# Lithiumversion_2019_09_02.net
KiCad netlist of a schematic drawn in EAGLE
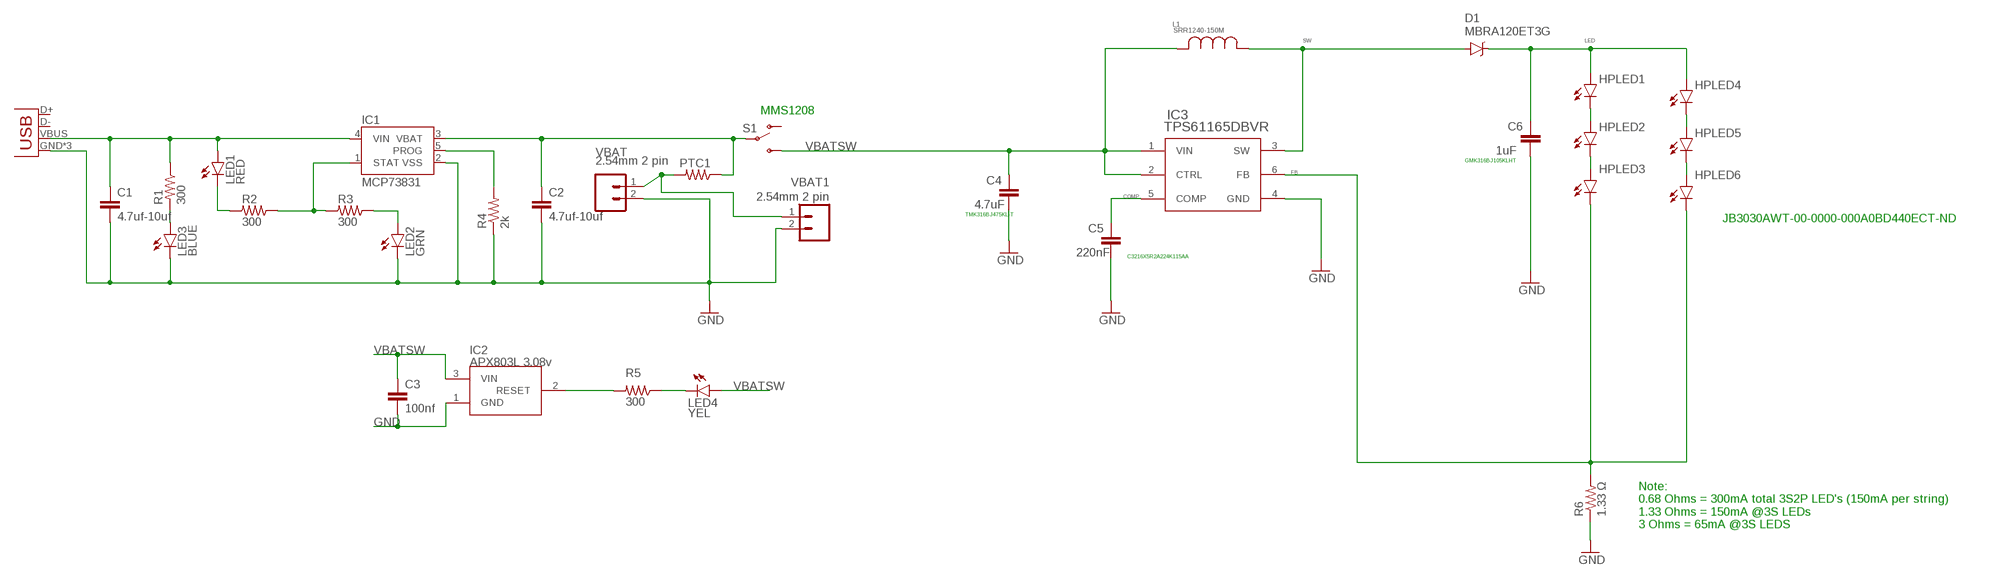
[diagram p0: schematic, sheet 1]

(export (version "E")
  (design (tool "Eeschema 10.0.6"))
  (components
    (comp (ref "C1")
      (value "4.7uf-10uf")
      (footprint "eagle-import:1206")
      (libsource (lib "eagle-import") (part "CAP1206"))
    )
    (comp (ref "C2")
      (value "4.7uf-10uf")
      (footprint "eagle-import:1206")
      (libsource (lib "eagle-import") (part "CAP1206"))
    )
    (comp (ref "C3")
      (value "100nf")
      (footprint "eagle-import:1206")
      (libsource (lib "eagle-import") (part "CAP1206"))
    )
    (comp (ref "C4")
      (value "4.7uF")
      (footprint "eagle-import:1206")
      (libsource (lib "eagle-import") (part "SparkFun-Passives_CAP1206"))
    )
    (comp (ref "C5")
      (value "220nF")
      (footprint "eagle-import:1206")
      (libsource (lib "eagle-import") (part "SparkFun-Passives_CAP1206"))
    )
    (comp (ref "C6")
      (value "1uF")
      (footprint "eagle-import:1206")
      (libsource (lib "eagle-import") (part "SparkFun-Passives_CAP1206"))
    )
    (comp (ref "D1")
      (value "MBRA120ET3G")
      (footprint "eagle-import:SMA-DIODE")
      (libsource (lib "eagle-import") (part "DIODE-SCHOTTKY-B340A"))
    )
    (comp (ref "HPLED1")
      (value "CREE_J_3030")
      (footprint "eagle-import:CREE_J_3030")
      (libsource (lib "eagle-import") (part "CREE_J_3030"))
    )
    (comp (ref "HPLED2")
      (value "CREE_J_3030")
      (footprint "eagle-import:CREE_J_3030")
      (libsource (lib "eagle-import") (part "CREE_J_3030"))
    )
    (comp (ref "HPLED3")
      (value "CREE_J_3030")
      (footprint "eagle-import:CREE_J_3030")
      (libsource (lib "eagle-import") (part "CREE_J_3030"))
    )
    (comp (ref "HPLED4")
      (value "CREE_J_3030")
      (footprint "eagle-import:CREE_J_3030")
      (libsource (lib "eagle-import") (part "CREE_J_3030"))
    )
    (comp (ref "HPLED5")
      (value "CREE_J_3030")
      (footprint "eagle-import:CREE_J_3030")
      (libsource (lib "eagle-import") (part "CREE_J_3030"))
    )
    (comp (ref "HPLED6")
      (value "CREE_J_3030")
      (footprint "eagle-import:CREE_J_3030")
      (libsource (lib "eagle-import") (part "CREE_J_3030"))
    )
    (comp (ref "IC1")
      (value "MCP73831")
      (footprint "eagle-import:SOT23-5")
      (libsource (lib "eagle-import") (part "MCP73831"))
    )
    (comp (ref "IC2")
      (value "APX803L 3.08v")
      (footprint "eagle-import:SOT23")
      (libsource (lib "eagle-import") (part "ADP160"))
    )
    (comp (ref "IC3")
      (value "TPS61165DBVR")
      (footprint "eagle-import:DBV6")
      (libsource (lib "eagle-import") (part "TPS61165DBVR"))
    )
    (comp (ref "JP3")
      (value "USB-MICROB")
      (footprint "eagle-import:USB-MICROB")
      (libsource (lib "eagle-import") (part "USB-MICROB"))
    )
    (comp (ref "L1")
      (value "SRR1240-150M")
      (footprint "eagle-import:IND_BOURNS_SRR1240")
      (fields (field (name "MANUFACTURER_PART_NUMBER") "SRR1240100M"))
      (libsource (lib "eagle-import") (part "SRR1240-100M"))
    )
    (comp (ref "LED1")
      (value "RED")
      (footprint "eagle-import:LED-1206")
      (libsource (lib "eagle-import") (part "LED1206"))
    )
    (comp (ref "LED2")
      (value "GRN")
      (footprint "eagle-import:LED-1206")
      (libsource (lib "eagle-import") (part "LED1206"))
    )
    (comp (ref "LED3")
      (value "BLUE")
      (footprint "eagle-import:LED-1206")
      (libsource (lib "eagle-import") (part "LED1206"))
    )
    (comp (ref "LED4")
      (value "YEL")
      (footprint "eagle-import:LED-1206")
      (libsource (lib "eagle-import") (part "LED1206"))
    )
    (comp (ref "PTC1")
      (value "RESISTOR1206")
      (footprint "eagle-import:1206")
      (libsource (lib "eagle-import") (part "SparkFun-Resistors_RESISTOR1206"))
    )
    (comp (ref "R1")
      (value "300")
      (footprint "eagle-import:1206")
      (libsource (lib "eagle-import") (part "SparkFun-Resistors_RESISTOR1206"))
    )
    (comp (ref "R2")
      (value "300")
      (footprint "eagle-import:1206")
      (libsource (lib "eagle-import") (part "SparkFun-Resistors_RESISTOR1206"))
    )
    (comp (ref "R3")
      (value "300")
      (footprint "eagle-import:1206")
      (libsource (lib "eagle-import") (part "SparkFun-Resistors_RESISTOR1206"))
    )
    (comp (ref "R4")
      (value "2k")
      (footprint "eagle-import:1206")
      (libsource (lib "eagle-import") (part "SparkFun-Resistors_RESISTOR1206"))
    )
    (comp (ref "R5")
      (value "300")
      (footprint "eagle-import:1206")
      (libsource (lib "eagle-import") (part "SparkFun-Resistors_RESISTOR1206"))
    )
    (comp (ref "R6")
      (value "1.33 Ω")
      (footprint "eagle-import:1206")
      (libsource (lib "eagle-import") (part "RESISTOR1206"))
    )
    (comp (ref "S1")
      (value "SWITCH-SPDTKIT")
      (footprint "eagle-import:SWITCH-SPDT_KIT")
      (libsource (lib "eagle-import") (part "SWITCH-SPDTKIT"))
    )
    (comp (ref "VBAT")
      (value "2.54mm 2 pin")
      (footprint "eagle-import:JST-2-PTH-VERT")
      (libsource (lib "eagle-import") (part "M02JST-PTH-VERT"))
    )
    (comp (ref "VBAT1")
      (value "2.54mm 2 pin")
      (footprint "eagle-import:JST-2-PTH-VERT")
      (libsource (lib "eagle-import") (part "M02JST-PTH-VERT"))
    )
  )
  (nets
    (net (code "1") (name "/COMP") (class "Default")
      (node (ref "C5") (pin "2") (pinfunction "2_2") (pintype "passive"))
      (node (ref "IC3") (pin "5") (pinfunction "COMP_5") (pintype "output"))
    )
    (net (code "2") (name "/FB") (class "Default")
      (node (ref "HPLED3") (pin "C") (pinfunction "C_C") (pintype "passive"))
      (node (ref "HPLED6") (pin "C") (pinfunction "C_C") (pintype "passive"))
      (node (ref "IC3") (pin "6") (pinfunction "FB_6") (pintype "input"))
      (node (ref "R6") (pin "2") (pinfunction "2_2") (pintype "passive"))
    )
    (net (code "3") (name "/LED") (class "Default")
      (node (ref "C6") (pin "2") (pinfunction "2_2") (pintype "passive"))
      (node (ref "D1") (pin "C") (pinfunction "C_C") (pintype "passive"))
      (node (ref "HPLED1") (pin "A") (pinfunction "A_A") (pintype "passive"))
      (node (ref "HPLED1") (pin "A2") (pinfunction "A_A2") (pintype "passive"))
      (node (ref "HPLED4") (pin "A") (pinfunction "A_A") (pintype "passive"))
      (node (ref "HPLED4") (pin "A2") (pinfunction "A_A2") (pintype "passive"))
    )
    (net (code "4") (name "/SW") (class "Default")
      (node (ref "D1") (pin "A") (pinfunction "A_A") (pintype "passive"))
      (node (ref "IC3") (pin "3") (pinfunction "SW_3") (pintype "input"))
      (node (ref "L1") (pin "1") (pinfunction "1_1") (pintype "passive"))
    )
    (net (code "5") (name "/VBATSW") (class "Default")
      (node (ref "C3") (pin "1") (pinfunction "1_1") (pintype "passive"))
      (node (ref "C4") (pin "2") (pinfunction "2_2") (pintype "passive"))
      (node (ref "IC2") (pin "3") (pinfunction "VIN_3") (pintype "bidirectional"))
      (node (ref "IC3") (pin "1") (pinfunction "VIN_1") (pintype "input"))
      (node (ref "IC3") (pin "2") (pinfunction "CTRL_2") (pintype "input"))
      (node (ref "L1") (pin "2") (pinfunction "2_2") (pintype "passive"))
      (node (ref "LED4") (pin "A") (pinfunction "A_A") (pintype "passive"))
      (node (ref "S1") (pin "3") (pinfunction "S_3") (pintype "passive"))
    )
    (net (code "6") (name "GND") (class "Default")
      (node (ref "C1") (pin "2") (pinfunction "2_2") (pintype "passive"))
      (node (ref "C2") (pin "2") (pinfunction "2_2") (pintype "passive"))
      (node (ref "C3") (pin "2") (pinfunction "2_2") (pintype "passive"))
      (node (ref "C4") (pin "1") (pinfunction "1_1") (pintype "passive"))
      (node (ref "C5") (pin "1") (pinfunction "1_1") (pintype "passive"))
      (node (ref "C6") (pin "1") (pinfunction "1_1") (pintype "passive"))
      (node (ref "IC1") (pin "2") (pinfunction "VSS_2") (pintype "power_in"))
      (node (ref "IC2") (pin "1") (pinfunction "GND_1") (pintype "bidirectional"))
      (node (ref "IC3") (pin "4") (pinfunction "GND_4") (pintype "output"))
      (node (ref "JP3") (pin "GND") (pinfunction "GND_GND") (pintype "bidirectional"))
      (node (ref "JP3") (pin "MT1") (pinfunction "GND_MT1") (pintype "bidirectional"))
      (node (ref "JP3") (pin "MT2") (pinfunction "GND_MT2") (pintype "bidirectional"))
      (node (ref "LED2") (pin "C") (pinfunction "C_C") (pintype "passive"))
      (node (ref "LED3") (pin "C") (pinfunction "C_C") (pintype "passive"))
      (node (ref "R4") (pin "1") (pinfunction "1_1") (pintype "passive"))
      (node (ref "R6") (pin "1") (pinfunction "1_1") (pintype "passive"))
      (node (ref "VBAT") (pin "2") (pinfunction "2_2") (pintype "passive"))
      (node (ref "VBAT1") (pin "2") (pinfunction "2_2") (pintype "passive"))
    )
    (net (code "7") (name "Net-(HPLED1-PadC)") (class "Default")
      (node (ref "HPLED1") (pin "C") (pinfunction "C_C") (pintype "passive"))
      (node (ref "HPLED2") (pin "A") (pinfunction "A_A") (pintype "passive"))
      (node (ref "HPLED2") (pin "A2") (pinfunction "A_A2") (pintype "passive"))
    )
    (net (code "8") (name "Net-(HPLED2-PadC)") (class "Default")
      (node (ref "HPLED2") (pin "C") (pinfunction "C_C") (pintype "passive"))
      (node (ref "HPLED3") (pin "A") (pinfunction "A_A") (pintype "passive"))
      (node (ref "HPLED3") (pin "A2") (pinfunction "A_A2") (pintype "passive"))
    )
    (net (code "9") (name "Net-(HPLED4-PadC)") (class "Default")
      (node (ref "HPLED4") (pin "C") (pinfunction "C_C") (pintype "passive"))
      (node (ref "HPLED5") (pin "A") (pinfunction "A_A") (pintype "passive"))
      (node (ref "HPLED5") (pin "A2") (pinfunction "A_A2") (pintype "passive"))
    )
    (net (code "10") (name "Net-(HPLED5-PadC)") (class "Default")
      (node (ref "HPLED5") (pin "C") (pinfunction "C_C") (pintype "passive"))
      (node (ref "HPLED6") (pin "A") (pinfunction "A_A") (pintype "passive"))
      (node (ref "HPLED6") (pin "A2") (pinfunction "A_A2") (pintype "passive"))
    )
    (net (code "11") (name "Net-(IC1-PROG)") (class "Default")
      (node (ref "IC1") (pin "5") (pinfunction "PROG_5") (pintype "input"))
      (node (ref "R4") (pin "2") (pinfunction "2_2") (pintype "passive"))
    )
    (net (code "12") (name "Net-(IC1-STAT)") (class "Default")
      (node (ref "IC1") (pin "1") (pinfunction "STAT_1") (pintype "output"))
      (node (ref "R2") (pin "1") (pinfunction "1_1") (pintype "passive"))
      (node (ref "R3") (pin "2") (pinfunction "2_2") (pintype "passive"))
    )
    (net (code "13") (name "Net-(IC1-VBAT)") (class "Default")
      (node (ref "C2") (pin "1") (pinfunction "1_1") (pintype "passive"))
      (node (ref "IC1") (pin "3") (pinfunction "VBAT_3") (pintype "power_in"))
      (node (ref "PTC1") (pin "1") (pinfunction "1_1") (pintype "passive"))
      (node (ref "S1") (pin "2") (pinfunction "P_2") (pintype "passive"))
    )
    (net (code "14") (name "Net-(IC1-VIN)") (class "Default")
      (node (ref "C1") (pin "1") (pinfunction "1_1") (pintype "passive"))
      (node (ref "IC1") (pin "4") (pinfunction "VIN_4") (pintype "power_in"))
      (node (ref "JP3") (pin "VBUS") (pinfunction "VBUS_VBUS") (pintype "bidirectional"))
      (node (ref "LED1") (pin "A") (pinfunction "A_A") (pintype "passive"))
      (node (ref "R1") (pin "1") (pinfunction "1_1") (pintype "passive"))
    )
    (net (code "15") (name "Net-(IC2-RESET)") (class "Default")
      (node (ref "IC2") (pin "2") (pinfunction "RESET_2") (pintype "bidirectional"))
      (node (ref "R5") (pin "2") (pinfunction "2_2") (pintype "passive"))
    )
    (net (code "16") (name "Net-(LED1-PadC)") (class "Default")
      (node (ref "LED1") (pin "C") (pinfunction "C_C") (pintype "passive"))
      (node (ref "R2") (pin "2") (pinfunction "2_2") (pintype "passive"))
    )
    (net (code "17") (name "Net-(LED2-PadA)") (class "Default")
      (node (ref "LED2") (pin "A") (pinfunction "A_A") (pintype "passive"))
      (node (ref "R3") (pin "1") (pinfunction "1_1") (pintype "passive"))
    )
    (net (code "18") (name "Net-(LED3-PadA)") (class "Default")
      (node (ref "LED3") (pin "A") (pinfunction "A_A") (pintype "passive"))
      (node (ref "R1") (pin "2") (pinfunction "2_2") (pintype "passive"))
    )
    (net (code "19") (name "Net-(LED4-PadC)") (class "Default")
      (node (ref "LED4") (pin "C") (pinfunction "C_C") (pintype "passive"))
      (node (ref "R5") (pin "1") (pinfunction "1_1") (pintype "passive"))
    )
    (net (code "20") (name "Net-(PTC1-Pad2)") (class "Default")
      (node (ref "PTC1") (pin "2") (pinfunction "2_2") (pintype "passive"))
      (node (ref "VBAT") (pin "1") (pinfunction "1_1") (pintype "passive"))
      (node (ref "VBAT1") (pin "1") (pinfunction "1_1") (pintype "passive"))
    )
    (net (code "21") (name "unconnected-(JP3-PadD+)") (class "Default")
      (node (ref "JP3") (pin "D+") (pinfunction "D+_D+") (pintype "bidirectional"))
    )
    (net (code "22") (name "unconnected-(JP3-PadD-)") (class "Default")
      (node (ref "JP3") (pin "D-") (pinfunction "D-_D-") (pintype "bidirectional"))
    )
    (net (code "23") (name "unconnected-(S1-O-Pad1)") (class "Default")
      (node (ref "S1") (pin "1") (pinfunction "O_1") (pintype "passive"))
    )
  )
)
